# Adafruit_ADXL326.net
KiCad netlist of a schematic drawn in EAGLE
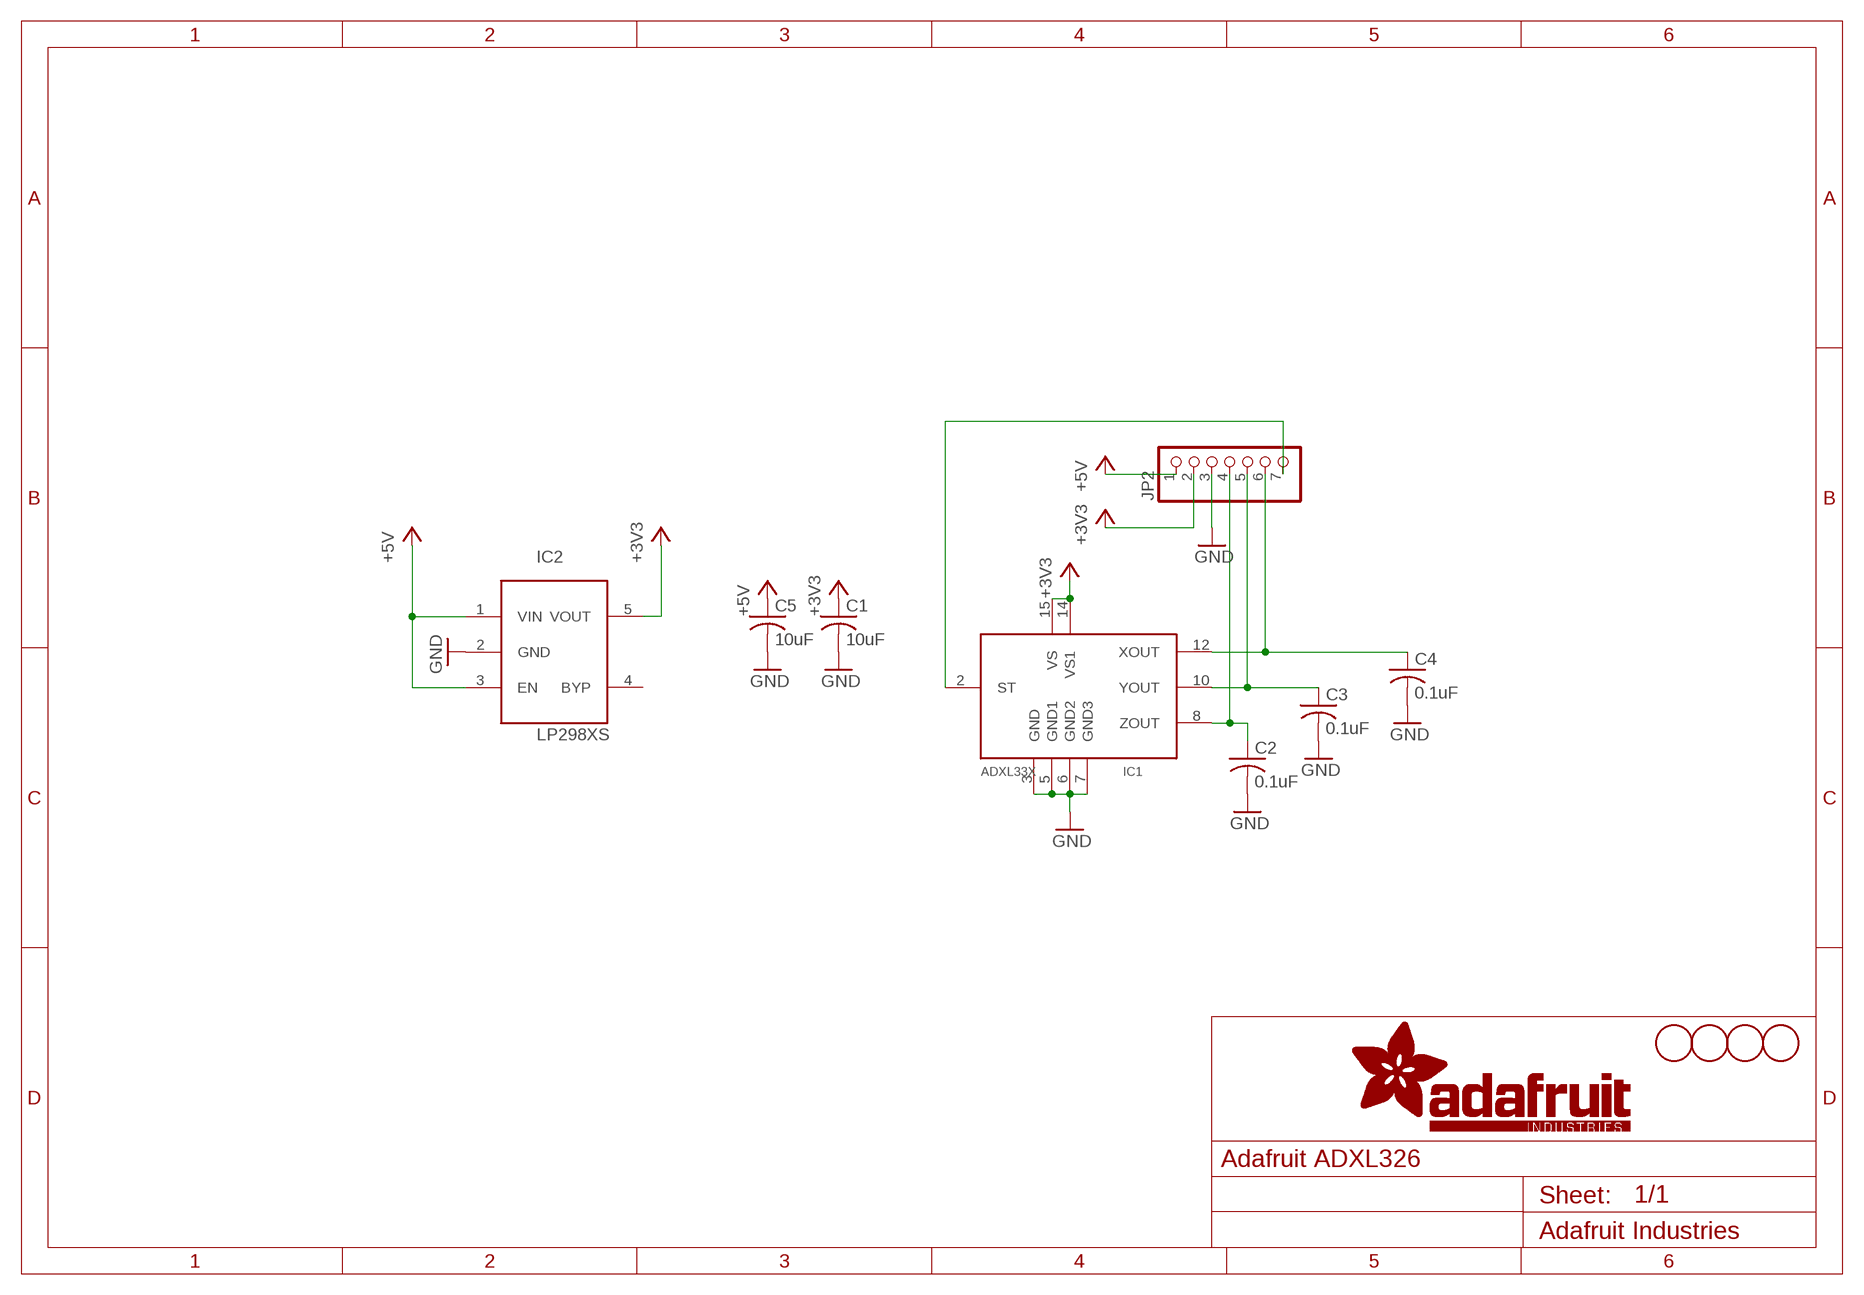
[diagram p0: schematic, sheet 1]

(export (version "E")
  (design (tool "Eeschema 10.0.6"))
  (components
    (comp (ref "C1")
      (value "10uF")
      (footprint "eagle-import:C0805K")
      (libsource (lib "eagle-import") (part "C-USC0805K"))
    )
    (comp (ref "C2")
      (value "0.1uF")
      (footprint "eagle-import:C0805K")
      (libsource (lib "eagle-import") (part "C-USC0805K"))
    )
    (comp (ref "C3")
      (value "0.1uF")
      (footprint "eagle-import:C0805K")
      (libsource (lib "eagle-import") (part "C-USC0805K"))
    )
    (comp (ref "C4")
      (value "0.1uF")
      (footprint "eagle-import:C0805K")
      (libsource (lib "eagle-import") (part "C-USC0805K"))
    )
    (comp (ref "C5")
      (value "10uF")
      (footprint "eagle-import:C0805K")
      (libsource (lib "eagle-import") (part "C-USC0805K"))
    )
    (comp (ref "IC1")
      (value "ADXL33X")
      (footprint "eagle-import:16LCSP")
      (libsource (lib "eagle-import") (part "ADXL33X"))
    )
    (comp (ref "IC2")
      (value "LP298XS")
      (footprint "eagle-import:SOT23-5L")
      (libsource (lib "eagle-import") (part "LP298XS"))
    )
    (comp (ref "JP2")
      (value "HEADER-1X7THICKER")
      (footprint "eagle-import:1X07_ROUND_76")
      (libsource (lib "eagle-import") (part "HEADER-1X7THICKER"))
    )
    (comp (ref "U$1")
      (value "FIDUCIAL")
      (footprint "eagle-import:FIDUCIAL_1MM")
      (libsource (lib "eagle-import") (part "FIDUCIAL"))
    )
    (comp (ref "U$2")
      (value "FIDUCIAL")
      (footprint "eagle-import:FIDUCIAL_1MM")
      (libsource (lib "eagle-import") (part "FIDUCIAL"))
    )
    (comp (ref "U$5")
      (value "MOUNTINGHOLE2.0")
      (footprint "eagle-import:MOUNTINGHOLE_2.0_PLATED")
      (libsource (lib "eagle-import") (part "MOUNTINGHOLE2.0"))
    )
    (comp (ref "U$8")
      (value "MOUNTINGHOLE2.0")
      (footprint "eagle-import:MOUNTINGHOLE_2.0_PLATED")
      (libsource (lib "eagle-import") (part "MOUNTINGHOLE2.0"))
    )
  )
  (nets
    (net (code "1") (name "+3V3") (class "Default")
      (node (ref "C1") (pin "1") (pinfunction "1_1") (pintype "passive"))
      (node (ref "IC1") (pin "14") (pinfunction "VS1_14") (pintype "power_in"))
      (node (ref "IC1") (pin "15") (pinfunction "VS_15") (pintype "power_in"))
      (node (ref "IC2") (pin "5") (pinfunction "VOUT_5") (pintype "bidirectional"))
      (node (ref "JP2") (pin "2") (pinfunction "2_2") (pintype "passive"))
    )
    (net (code "2") (name "+5V") (class "Default")
      (node (ref "C5") (pin "1") (pinfunction "1_1") (pintype "passive"))
      (node (ref "IC2") (pin "1") (pinfunction "VIN_1") (pintype "bidirectional"))
      (node (ref "IC2") (pin "3") (pinfunction "EN_3") (pintype "bidirectional"))
      (node (ref "JP2") (pin "1") (pinfunction "1_1") (pintype "passive"))
    )
    (net (code "3") (name "GND") (class "Default")
      (node (ref "C1") (pin "2") (pinfunction "2_2") (pintype "passive"))
      (node (ref "C2") (pin "2") (pinfunction "2_2") (pintype "passive"))
      (node (ref "C3") (pin "2") (pinfunction "2_2") (pintype "passive"))
      (node (ref "C4") (pin "2") (pinfunction "2_2") (pintype "passive"))
      (node (ref "C5") (pin "2") (pinfunction "2_2") (pintype "passive"))
      (node (ref "IC1") (pin "3") (pinfunction "GND_3") (pintype "power_in"))
      (node (ref "IC1") (pin "5") (pinfunction "GND1_5") (pintype "power_in"))
      (node (ref "IC1") (pin "6") (pinfunction "GND2_6") (pintype "power_in"))
      (node (ref "IC1") (pin "7") (pinfunction "GND3_7") (pintype "power_in"))
      (node (ref "IC2") (pin "2") (pinfunction "GND_2") (pintype "bidirectional"))
      (node (ref "JP2") (pin "3") (pinfunction "3_3") (pintype "passive"))
    )
    (net (code "4") (name "Net-(IC1-ST)") (class "Default")
      (node (ref "IC1") (pin "2") (pinfunction "ST_2") (pintype "input"))
      (node (ref "JP2") (pin "7") (pinfunction "7_7") (pintype "passive"))
    )
    (net (code "5") (name "Net-(IC1-XOUT)") (class "Default")
      (node (ref "C4") (pin "1") (pinfunction "1_1") (pintype "passive"))
      (node (ref "IC1") (pin "12") (pinfunction "XOUT_12") (pintype "output"))
      (node (ref "JP2") (pin "6") (pinfunction "6_6") (pintype "passive"))
    )
    (net (code "6") (name "Net-(IC1-YOUT)") (class "Default")
      (node (ref "C3") (pin "1") (pinfunction "1_1") (pintype "passive"))
      (node (ref "IC1") (pin "10") (pinfunction "YOUT_10") (pintype "output"))
      (node (ref "JP2") (pin "5") (pinfunction "5_5") (pintype "passive"))
    )
    (net (code "7") (name "Net-(IC1-ZOUT)") (class "Default")
      (node (ref "C2") (pin "1") (pinfunction "1_1") (pintype "passive"))
      (node (ref "IC1") (pin "8") (pinfunction "ZOUT_8") (pintype "output"))
      (node (ref "JP2") (pin "4") (pinfunction "4_4") (pintype "passive"))
    )
    (net (code "8") (name "unconnected-(IC2-BYP-Pad4)") (class "Default")
      (node (ref "IC2") (pin "4") (pinfunction "BYP_4") (pintype "bidirectional"))
    )
  )
)
